# Sheet1.net
KiCad netlist of a schematic drawn in Altium Designer
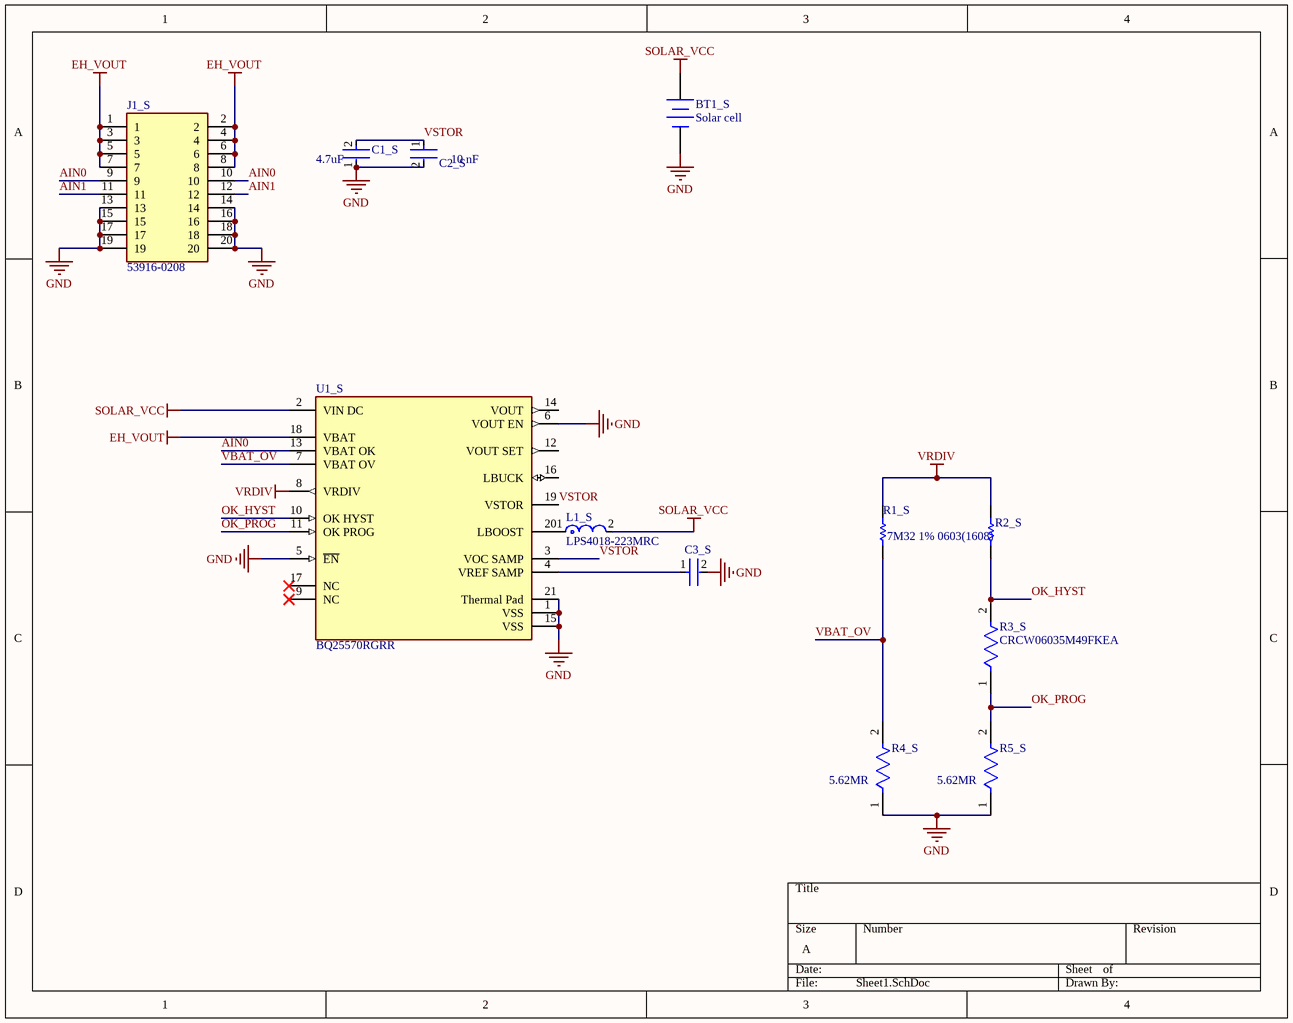
[diagram p0: Sheet1.SchDoc]

(export (version "E")
  (design (tool "Eeschema 10.0.6"))
  (components
    (comp (ref "BT1_S")
      (value "Solar cell")
      (footprint "BAT-2")
      (description "Multicell Battery")
      (fields (field (name "PUBLISHER") "Altium Limited"))
      (libsource (lib "Miscellaneous Devices") (part "Battery"))
    )
    (comp (ref "C1_S")
      (value "GRM188R60J475KE19D")
      (footprint "FP-GRM188-0_1-MFG")
      (description "CAP CER 4.7UF 6.3V X5R 0603")
      (fields
        (field (name "CAPACITANCE") "4.7uF")
        (field (name "VOLTAGE") "6.3V")
        (field (name "TOLERANCE") "10%")
      )
      (libsource (lib "Altium Content Vault") (part "236180d848d6139a670b325ea6854c9"))
    )
    (comp (ref "C2_S")
      (value "CC0603KRX7R9BB103")
      (footprint "FP-CC0603-DA-MFG")
      (description "CAP CER 10000PF 50V X7R 0603")
      (fields
        (field (name "TOLERANCE") "0.1")
        (field (name "MANUFACTURER") "YAGEO")
        (field (name "CAPACITANCE") "10 nF")
      )
      (libsource (lib "Altium Content Vault") (part "11868f565c42a9108669ba33697ecf6"))
    )
    (comp (ref "C3_S")
      (value "CC0603KRX7R9BB103")
      (footprint "FP-CC0603-DA-MFG")
      (description "CAP CER 10000PF 50V X7R 0603")
      (fields (field (name "TOLERANCE") "0.1") (field (name "MANUFACTURER") "YAGEO"))
      (libsource (lib "Altium Content Vault") (part "11868f565c42a9108669ba33697ecf6"))
    )
    (comp (ref "J1_S")
      (value "53916-0208")
      (footprint "MOLEX-  539160208")
      (libsource (lib "52991-0208") (part "53916-0208"))
    )
    (comp (ref "L1_S")
      (value "LPS4018-223MRC")
      (footprint "FP-LPS4018-MFG")
      (description "Fixed Inductors LPS4018 Low Profile 22uH 0.9A 20% SMD")
      (fields (field (name "TOLERANCE") "20%"))
      (libsource (lib "Altium Content Vault") (part "4cc4b267dca4c8e51f7102f422741d8"))
    )
    (comp (ref "R1_S")
      (value "7M32 1% 0603(1608)")
      (footprint "RESC0603(1608)_N")
      (description "7M32 0.1W 1% 0603 (1608 Metric)  SMD")
      (fields (field (name "POWER") "0.1 W") (field (name "TOLERANCE") "1 %"))
      (libsource (lib "Altium Content Vault") (part "RES"))
    )
    (comp (ref "R2_S")
      (value "CRCW06031M87FKEA")
      (footprint "RESC1609X50X30ML10T20")
      (fields (field (name "MANUFACTURER") "Vishay Dale"))
      (libsource (lib "Altium Content Vault") (part "RES"))
    )
    (comp (ref "R3_S")
      (value "CRCW06035M49FKEA")
      (footprint "FP-CRCW0603-e3-IPC_C")
      (description "RES Thick Film, 5.49MΩ, 1%, 0.1W, 100ppm/°C, 0603")
      (fields (field (name "TOLERANCE") "1%"))
      (libsource (lib "Altium Content Vault") (part "1029c3af85768c4190bb7ad29bc67b5"))
    )
    (comp (ref "R4_S")
      (value "CRCW06035M62FKEA")
      (footprint "FP-CRCW0603-e3-IPC_B")
      (description "RES Thick Film, 5.62MΩ, 1%, 0.1W, 100ppm/°C, 0603")
      (fields (field (name "RESISTANCE") "5.62MR") (field (name "TOLERANCE") "1%"))
      (libsource (lib "Altium Content Vault") (part "1029c3af85768c4190bb7ad29bc67b5"))
    )
    (comp (ref "R5_S")
      (value "CRCW06035M62FKEA")
      (footprint "FP-CRCW0603-e3-IPC_B")
      (description "RES Thick Film, 5.62MΩ, 1%, 0.1W, 100ppm/°C, 0603")
      (fields (field (name "RESISTANCE") "5.62MR") (field (name "TOLERANCE") "1%"))
      (libsource (lib "Altium Content Vault") (part "1029c3af85768c4190bb7ad29bc67b5"))
    )
    (comp (ref "U1_S")
      (value "BQ25570RGRR")
      (footprint "FP-RGR0020A-MFG")
      (description "IC ENERGY HARV CTRLR BATT 20VQFN")
      (libsource (lib "Altium Content Vault") (part "27933bacb7c13f6eb3b89b25cfc7317"))
    )
  )
  (nets
    (net (code "1") (name "/AIN0") (class "Default")
      (node (ref "J1_S") (pin "10") (pinfunction "10_10") (pintype "passive"))
      (node (ref "J1_S") (pin "9") (pinfunction "9_9") (pintype "passive"))
      (node (ref "U1_S") (pin "13") (pinfunction "VBAT_OK_13") (pintype "power_in"))
    )
    (net (code "2") (name "/AIN1") (class "Default")
      (node (ref "J1_S") (pin "11") (pinfunction "11_11") (pintype "passive"))
      (node (ref "J1_S") (pin "12") (pinfunction "12_12") (pintype "passive"))
    )
    (net (code "3") (name "/OK_HYST") (class "Default")
      (node (ref "R2_S") (pin "1") (pinfunction "1_1") (pintype "passive"))
      (node (ref "R3_S") (pin "2") (pinfunction "2_2") (pintype "passive"))
      (node (ref "U1_S") (pin "10") (pinfunction "OK_HYST_10") (pintype "input"))
    )
    (net (code "4") (name "/OK_PROG") (class "Default")
      (node (ref "R3_S") (pin "1") (pinfunction "1_1") (pintype "passive"))
      (node (ref "R5_S") (pin "2") (pinfunction "2_2") (pintype "passive"))
      (node (ref "U1_S") (pin "11") (pinfunction "OK_PROG_11") (pintype "input"))
    )
    (net (code "5") (name "/VBAT_OV") (class "Default")
      (node (ref "R1_S") (pin "1") (pinfunction "1_1") (pintype "passive"))
      (node (ref "R4_S") (pin "2") (pinfunction "2_2") (pintype "passive"))
      (node (ref "U1_S") (pin "7") (pinfunction "VBAT_OV_7") (pintype "power_in"))
    )
    (net (code "6") (name "/VSTOR") (class "Default")
      (node (ref "C1_S") (pin "2") (pinfunction "2_2") (pintype "passive"))
      (node (ref "C2_S") (pin "1") (pinfunction "1_1") (pintype "passive"))
      (node (ref "U1_S") (pin "19") (pinfunction "VSTOR_19") (pintype "passive"))
      (node (ref "U1_S") (pin "3") (pinfunction "VOC_SAMP_3") (pintype "power_in"))
    )
    (net (code "7") (name "EH_VOUT") (class "Default")
      (node (ref "J1_S") (pin "1") (pinfunction "1_1") (pintype "passive"))
      (node (ref "J1_S") (pin "2") (pinfunction "2_2") (pintype "passive"))
      (node (ref "J1_S") (pin "3") (pinfunction "3_3") (pintype "passive"))
      (node (ref "J1_S") (pin "4") (pinfunction "4_4") (pintype "passive"))
      (node (ref "J1_S") (pin "5") (pinfunction "5_5") (pintype "passive"))
      (node (ref "J1_S") (pin "6") (pinfunction "6_6") (pintype "passive"))
      (node (ref "J1_S") (pin "7") (pinfunction "7_7") (pintype "passive"))
      (node (ref "J1_S") (pin "8") (pinfunction "8_8") (pintype "passive"))
      (node (ref "U1_S") (pin "18") (pinfunction "VBAT_18") (pintype "power_in"))
    )
    (net (code "8") (name "GND") (class "Default")
      (node (ref "BT1_S") (pin "2") (pinfunction "-_2") (pintype "passive"))
      (node (ref "C1_S") (pin "1") (pinfunction "1_1") (pintype "passive"))
      (node (ref "C2_S") (pin "2") (pinfunction "2_2") (pintype "passive"))
      (node (ref "C3_S") (pin "2") (pinfunction "2_2") (pintype "passive"))
      (node (ref "J1_S") (pin "13") (pinfunction "13_13") (pintype "passive"))
      (node (ref "J1_S") (pin "14") (pinfunction "14_14") (pintype "passive"))
      (node (ref "J1_S") (pin "15") (pinfunction "15_15") (pintype "passive"))
      (node (ref "J1_S") (pin "16") (pinfunction "16_16") (pintype "passive"))
      (node (ref "J1_S") (pin "17") (pinfunction "17_17") (pintype "passive"))
      (node (ref "J1_S") (pin "18") (pinfunction "18_18") (pintype "passive"))
      (node (ref "J1_S") (pin "19") (pinfunction "19_19") (pintype "passive"))
      (node (ref "J1_S") (pin "20") (pinfunction "20_20") (pintype "passive"))
      (node (ref "R4_S") (pin "1") (pinfunction "1_1") (pintype "passive"))
      (node (ref "R5_S") (pin "1") (pinfunction "1_1") (pintype "passive"))
      (node (ref "U1_S") (pin "1") (pinfunction "VSS_1") (pintype "power_in"))
      (node (ref "U1_S") (pin "15") (pinfunction "VSS_15") (pintype "power_in"))
      (node (ref "U1_S") (pin "21") (pinfunction "Thermal_Pad_21") (pintype "passive"))
      (node (ref "U1_S") (pin "5") (pinfunction "~{EN}_5") (pintype "input"))
      (node (ref "U1_S") (pin "6") (pinfunction "VOUT_EN_6") (pintype "output"))
    )
    (net (code "9") (name "Net-(U1_S-LBOOST)") (class "Default")
      (node (ref "L1_S") (pin "1") (pinfunction "1_1") (pintype "passive"))
      (node (ref "U1_S") (pin "20") (pinfunction "LBOOST_20") (pintype "passive"))
    )
    (net (code "10") (name "Net-(U1_S-VREF_SAMP)") (class "Default")
      (node (ref "C3_S") (pin "1") (pinfunction "1_1") (pintype "passive"))
      (node (ref "U1_S") (pin "4") (pinfunction "VREF_SAMP_4") (pintype "passive"))
    )
    (net (code "11") (name "SOLAR_VCC") (class "Default")
      (node (ref "BT1_S") (pin "1") (pinfunction "+_1") (pintype "passive"))
      (node (ref "L1_S") (pin "2") (pinfunction "2_2") (pintype "passive"))
      (node (ref "U1_S") (pin "2") (pinfunction "VIN_DC_2") (pintype "power_in"))
    )
    (net (code "12") (name "VRDIV") (class "Default")
      (node (ref "R1_S") (pin "2") (pinfunction "2_2") (pintype "passive"))
      (node (ref "R2_S") (pin "2") (pinfunction "2_2") (pintype "passive"))
      (node (ref "U1_S") (pin "8") (pinfunction "VRDIV_8") (pintype "output"))
    )
    (net (code "13") (name "unconnected-(U1_S-LBUCK-Pad16)") (class "Default")
      (node (ref "U1_S") (pin "16") (pinfunction "LBUCK_16") (pintype "bidirectional"))
    )
    (net (code "14") (name "unconnected-(U1_S-NC-Pad9)") (class "Default")
      (node (ref "U1_S") (pin "9") (pinfunction "NC_9") (pintype "passive+no_connect"))
    )
    (net (code "15") (name "unconnected-(U1_S-NC-Pad17)") (class "Default")
      (node (ref "U1_S") (pin "17") (pinfunction "NC_17") (pintype "passive+no_connect"))
    )
    (net (code "16") (name "unconnected-(U1_S-VOUT-Pad14)") (class "Default")
      (node (ref "U1_S") (pin "14") (pinfunction "VOUT_14") (pintype "output"))
    )
    (net (code "17") (name "unconnected-(U1_S-VOUT_SET-Pad12)") (class "Default")
      (node (ref "U1_S") (pin "12") (pinfunction "VOUT_SET_12") (pintype "output"))
    )
  )
)
